# PSU.net
KiCad netlist of a schematic drawn in Altium Designer
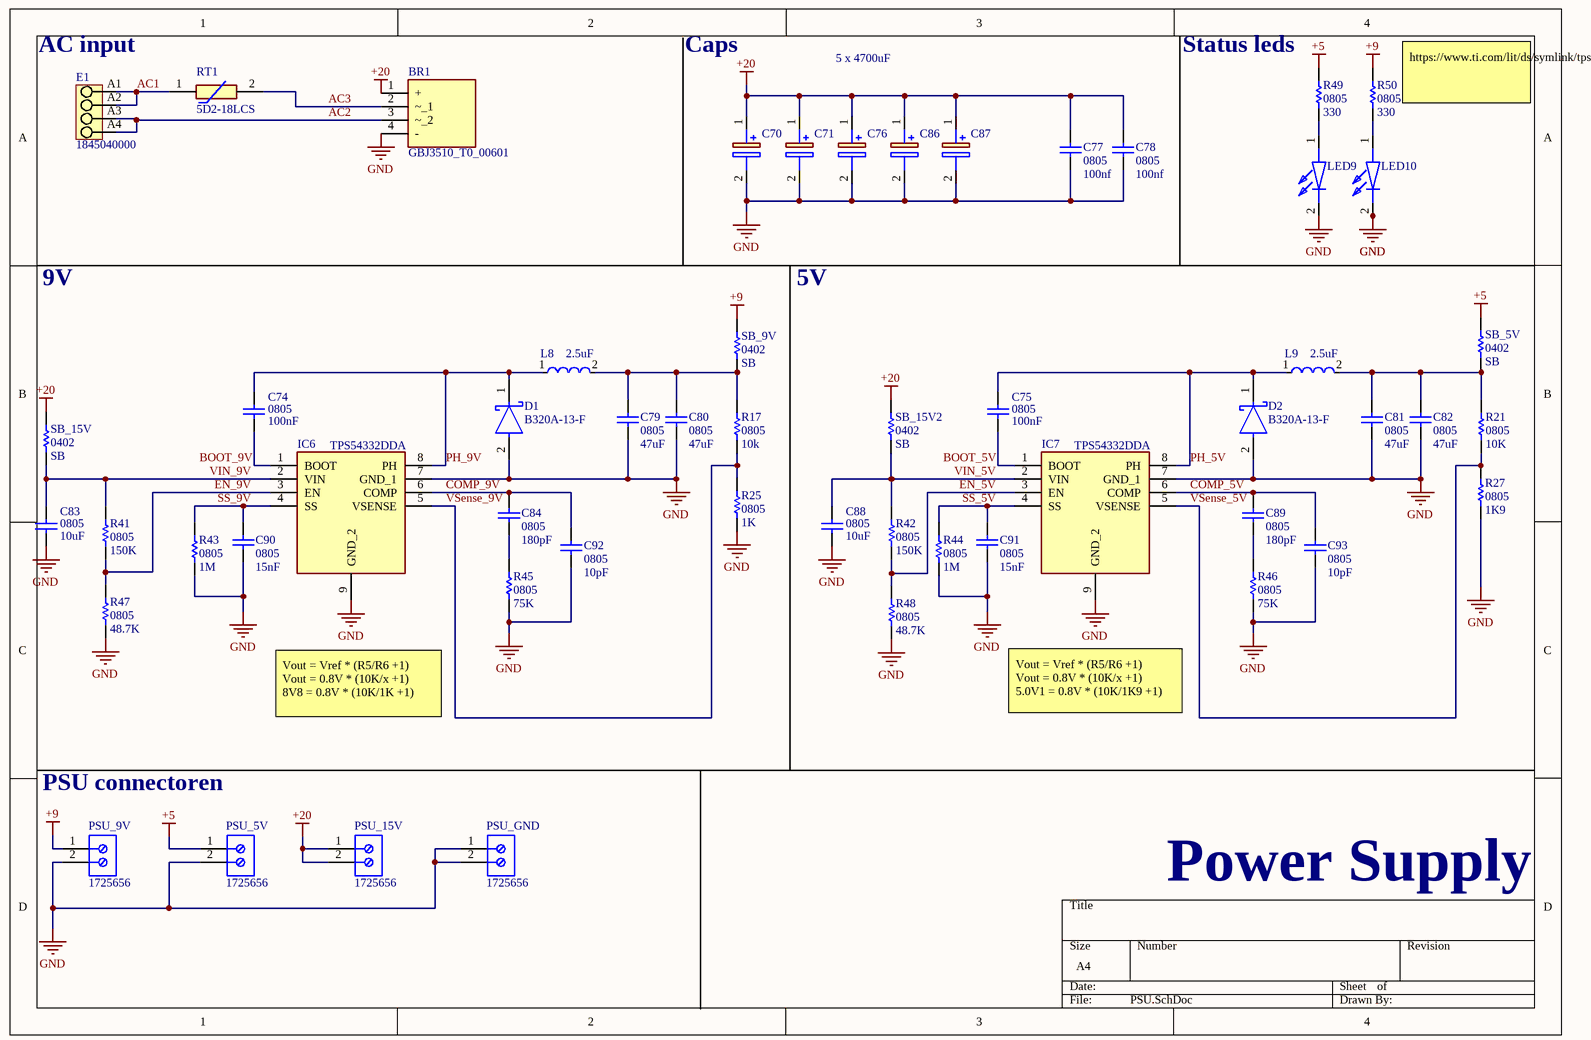
[diagram p0: PSU.SchDoc]

(export (version "E")
  (design (tool "Eeschema 10.0.6"))
  (components
    (comp (ref "BR1")
      (value "GBJ3510_T0_00601")
      (footprint "SamacSys:GBJ3510_T0_00601")
      (description "Bridge Rectifier")
      (fields (field (name "MOUSER PART NUMBER") "241-GBJ3510_T0_00601"))
      (libsource (lib "*") (part "GBJ3510_T0_00601"))
    )
    (comp (ref "C70")
      (value "UFW1V472MHD")
      (footprint "SamacSys:CAPPRD750W80D1825H3750")
      (description "Capacitor Polarised")
      (fields (field (name "MOUSER PART NUMBER") "647-UFW1V472MHD"))
      (libsource (lib "*") (part "UFW1V472MHD"))
    )
    (comp (ref "C71")
      (value "UFW1V472MHD")
      (footprint "SamacSys:CAPPRD750W80D1825H3750")
      (description "Capacitor Polarised")
      (fields (field (name "MOUSER PART NUMBER") "647-UFW1V472MHD"))
      (libsource (lib "*") (part "UFW1V472MHD"))
    )
    (comp (ref "C74")
      (value "0805")
      (footprint "6-0805_N")
      (description "Capacitor")
      (fields (field (name "ALTIUM_VALUE") "100nF") (field (name "PUBLISHER") "Altium Limited"))
      (libsource (lib "Miscellaneous Devices") (part "Cap"))
    )
    (comp (ref "C75")
      (value "0805")
      (footprint "6-0805_N")
      (description "Capacitor")
      (fields (field (name "ALTIUM_VALUE") "100nF") (field (name "PUBLISHER") "Altium Limited"))
      (libsource (lib "Miscellaneous Devices") (part "Cap"))
    )
    (comp (ref "C76")
      (value "UFW1V472MHD")
      (footprint "SamacSys:CAPPRD750W80D1825H3750")
      (description "Capacitor Polarised")
      (fields (field (name "MOUSER PART NUMBER") "647-UFW1V472MHD"))
      (libsource (lib "*") (part "UFW1V472MHD"))
    )
    (comp (ref "C77")
      (value "0805")
      (footprint "6-0805_N")
      (description "Capacitor")
      (fields (field (name "ALTIUM_VALUE") "100nf") (field (name "PUBLISHER") "Altium Limited"))
      (libsource (lib "Miscellaneous Devices") (part "Cap"))
    )
    (comp (ref "C78")
      (value "0805")
      (footprint "6-0805_N")
      (description "Capacitor")
      (fields (field (name "ALTIUM_VALUE") "100nf") (field (name "PUBLISHER") "Altium Limited"))
      (libsource (lib "Miscellaneous Devices") (part "Cap"))
    )
    (comp (ref "C79")
      (value "0805")
      (footprint "6-0805_N")
      (description "Capacitor")
      (fields (field (name "ALTIUM_VALUE") "47uF") (field (name "PUBLISHER") "Altium Limited"))
      (libsource (lib "Miscellaneous Devices") (part "Cap"))
    )
    (comp (ref "C80")
      (value "0805")
      (footprint "6-0805_N")
      (description "Capacitor")
      (fields (field (name "ALTIUM_VALUE") "47uF") (field (name "PUBLISHER") "Altium Limited"))
      (libsource (lib "Miscellaneous Devices") (part "Cap"))
    )
    (comp (ref "C81")
      (value "0805")
      (footprint "6-0805_N")
      (description "Capacitor")
      (fields (field (name "ALTIUM_VALUE") "47uF") (field (name "PUBLISHER") "Altium Limited"))
      (libsource (lib "Miscellaneous Devices") (part "Cap"))
    )
    (comp (ref "C82")
      (value "0805")
      (footprint "6-0805_N")
      (description "Capacitor")
      (fields (field (name "ALTIUM_VALUE") "47uF") (field (name "PUBLISHER") "Altium Limited"))
      (libsource (lib "Miscellaneous Devices") (part "Cap"))
    )
    (comp (ref "C83")
      (value "0805")
      (footprint "6-0805_N")
      (description "Capacitor")
      (fields (field (name "ALTIUM_VALUE") "10uF") (field (name "PUBLISHER") "Altium Limited"))
      (libsource (lib "Miscellaneous Devices") (part "Cap"))
    )
    (comp (ref "C84")
      (value "0805")
      (footprint "6-0805_N")
      (description "Capacitor")
      (fields (field (name "ALTIUM_VALUE") "180pF") (field (name "PUBLISHER") "Altium Limited"))
      (libsource (lib "Miscellaneous Devices") (part "Cap"))
    )
    (comp (ref "C86")
      (value "UFW1V472MHD")
      (footprint "SamacSys:CAPPRD750W80D1825H3750")
      (description "Capacitor Polarised")
      (fields (field (name "MOUSER PART NUMBER") "647-UFW1V472MHD"))
      (libsource (lib "*") (part "UFW1V472MHD"))
    )
    (comp (ref "C87")
      (value "UFW1V472MHD")
      (footprint "SamacSys:CAPPRD750W80D1825H3750")
      (description "Capacitor Polarised")
      (fields (field (name "MOUSER PART NUMBER") "647-UFW1V472MHD"))
      (libsource (lib "*") (part "UFW1V472MHD"))
    )
    (comp (ref "C88")
      (value "0805")
      (footprint "6-0805_N")
      (description "Capacitor")
      (fields (field (name "ALTIUM_VALUE") "10uF") (field (name "PUBLISHER") "Altium Limited"))
      (libsource (lib "Miscellaneous Devices") (part "Cap"))
    )
    (comp (ref "C89")
      (value "0805")
      (footprint "6-0805_N")
      (description "Capacitor")
      (fields (field (name "ALTIUM_VALUE") "180pF") (field (name "PUBLISHER") "Altium Limited"))
      (libsource (lib "Miscellaneous Devices") (part "Cap"))
    )
    (comp (ref "C90")
      (value "0805")
      (footprint "6-0805_N")
      (description "Capacitor")
      (fields (field (name "ALTIUM_VALUE") "15nF") (field (name "PUBLISHER") "Altium Limited"))
      (libsource (lib "Miscellaneous Devices") (part "Cap"))
    )
    (comp (ref "C91")
      (value "0805")
      (footprint "6-0805_N")
      (description "Capacitor")
      (fields (field (name "ALTIUM_VALUE") "15nF") (field (name "PUBLISHER") "Altium Limited"))
      (libsource (lib "Miscellaneous Devices") (part "Cap"))
    )
    (comp (ref "C92")
      (value "0805")
      (footprint "6-0805_N")
      (description "Capacitor")
      (fields (field (name "ALTIUM_VALUE") "10pF") (field (name "PUBLISHER") "Altium Limited"))
      (libsource (lib "Miscellaneous Devices") (part "Cap"))
    )
    (comp (ref "C93")
      (value "0805")
      (footprint "6-0805_N")
      (description "Capacitor")
      (fields (field (name "ALTIUM_VALUE") "10pF") (field (name "PUBLISHER") "Altium Limited"))
      (libsource (lib "Miscellaneous Devices") (part "Cap"))
    )
    (comp (ref "D1")
      (value "B320A-13-F")
      (footprint "FP-SMA-MFG")
      (description "DIODE SCHOTTKY 20V 3A SMA")
      (fields
        (field (name "MANUFACTURER") "Diodes Inc.")
        (field (name "OCTOPART") "https://octopart.com/b320a-13-f-diodes+inc.-325803")
      )
      (libsource (lib "Altium Content Vault") (part "1d6ec82d83fb6aee721767c19dac4b9"))
    )
    (comp (ref "D2")
      (value "B320A-13-F")
      (footprint "FP-SMA-MFG")
      (description "DIODE SCHOTTKY 20V 3A SMA")
      (fields
        (field (name "MANUFACTURER") "Diodes Inc.")
        (field (name "OCTOPART") "https://octopart.com/b320a-13-f-diodes+inc.-325803")
      )
      (libsource (lib "Altium Content Vault") (part "1d6ec82d83fb6aee721767c19dac4b9"))
    )
    (comp (ref "E1")
      (value "1845040000")
      (footprint "LM_3_5_90_04")
      (description "OMNIMATE Signal - series LM")
      (fields (field (name "MANUFACTURER") "Weidmueller"))
      (libsource (lib "Altium Content Vault") (part "Terminal_04_1x04"))
    )
    (comp (ref "IC6")
      (value "TPS54332DDA")
      (footprint "SamacSys:SOIC127P600X170-9N")
      (description "Integrated Circuit")
      (fields (field (name "MOUSER PART NUMBER") "595-TPS54332DDA"))
      (libsource (lib "*") (part "TPS54332DDA"))
    )
    (comp (ref "IC7")
      (value "TPS54332DDA")
      (footprint "SamacSys:SOIC127P600X170-9N")
      (description "Integrated Circuit")
      (fields (field (name "MOUSER PART NUMBER") "595-TPS54332DDA"))
      (libsource (lib "*") (part "TPS54332DDA"))
    )
    (comp (ref "L8")
      (value "2.5uF")
      (footprint "710-74437346025")
      (description "SMD")
      (libsource (lib "AMP") (part "710-74437346025"))
    )
    (comp (ref "L9")
      (value "2.5uF")
      (footprint "710-74437346025")
      (description "SMD")
      (libsource (lib "AMP") (part "710-74437346025"))
    )
    (comp (ref "LED9")
      (value "ELM70303GD")
      (footprint "SamacSys:ELM70303GD")
      (description "LED")
      (fields (field (name "MOUSER PART NUMBER") "749-ELM70303GD"))
      (libsource (lib "SamacSys") (part "ELM70303GD"))
    )
    (comp (ref "LED10")
      (value "ELM70303GD")
      (footprint "SamacSys:ELM70303GD")
      (description "LED")
      (fields (field (name "MOUSER PART NUMBER") "749-ELM70303GD"))
      (libsource (lib "SamacSys") (part "ELM70303GD"))
    )
    (comp (ref "PSU_5V")
      (value "1725656")
      (footprint "PHOE-1725656-2")
      (description "Male Header, Pitch 2.54 mm, 1 x 2 Position, Height 9 mm, Tail Length 3.5 mm")
      (fields (field (name "MANUFACTURER") "Phoenix Contact"))
      (libsource (lib "Altium Content Vault") (part "CN-1P-F-TB2"))
    )
    (comp (ref "PSU_9V")
      (value "1725656")
      (footprint "PHOE-1725656-2")
      (description "Male Header, Pitch 2.54 mm, 1 x 2 Position, Height 9 mm, Tail Length 3.5 mm")
      (fields (field (name "MANUFACTURER") "Phoenix Contact"))
      (libsource (lib "Altium Content Vault") (part "CN-1P-F-TB2"))
    )
    (comp (ref "PSU_15V")
      (value "1725656")
      (footprint "PHOE-1725656-2")
      (description "Male Header, Pitch 2.54 mm, 1 x 2 Position, Height 9 mm, Tail Length 3.5 mm")
      (fields (field (name "MANUFACTURER") "Phoenix Contact"))
      (libsource (lib "Altium Content Vault") (part "CN-1P-F-TB2"))
    )
    (comp (ref "PSU_GND")
      (value "1725656")
      (footprint "PHOE-1725656-2")
      (description "Male Header, Pitch 2.54 mm, 1 x 2 Position, Height 9 mm, Tail Length 3.5 mm")
      (fields (field (name "MANUFACTURER") "Phoenix Contact"))
      (libsource (lib "Altium Content Vault") (part "CN-1P-F-TB2"))
    )
    (comp (ref "R17")
      (value "0805")
      (footprint "6-0805_N")
      (description "Resistor")
      (fields (field (name "ALTIUM_VALUE") "10k") (field (name "PUBLISHER") "Altium Limited"))
      (libsource (lib "Miscellaneous Devices") (part "Res1"))
    )
    (comp (ref "R21")
      (value "0805")
      (footprint "6-0805_N")
      (description "Resistor")
      (fields (field (name "ALTIUM_VALUE") "10K") (field (name "PUBLISHER") "Altium Limited"))
      (libsource (lib "Miscellaneous Devices") (part "Res1"))
    )
    (comp (ref "R25")
      (value "0805")
      (footprint "6-0805_N")
      (description "Resistor")
      (fields (field (name "ALTIUM_VALUE") "1K") (field (name "PUBLISHER") "Altium Limited"))
      (libsource (lib "Miscellaneous Devices") (part "Res1"))
    )
    (comp (ref "R27")
      (value "0805")
      (footprint "6-0805_N")
      (description "Resistor")
      (fields (field (name "ALTIUM_VALUE") "1K9") (field (name "PUBLISHER") "Altium Limited"))
      (libsource (lib "Miscellaneous Devices") (part "Res1"))
    )
    (comp (ref "R41")
      (value "0805")
      (footprint "6-0805_N")
      (description "Resistor")
      (fields (field (name "ALTIUM_VALUE") "150K") (field (name "PUBLISHER") "Altium Limited"))
      (libsource (lib "Miscellaneous Devices") (part "Res1"))
    )
    (comp (ref "R42")
      (value "0805")
      (footprint "6-0805_N")
      (description "Resistor")
      (fields (field (name "ALTIUM_VALUE") "150K") (field (name "PUBLISHER") "Altium Limited"))
      (libsource (lib "Miscellaneous Devices") (part "Res1"))
    )
    (comp (ref "R43")
      (value "0805")
      (footprint "6-0805_N")
      (description "Resistor")
      (fields (field (name "ALTIUM_VALUE") "1M") (field (name "PUBLISHER") "Altium Limited"))
      (libsource (lib "Miscellaneous Devices") (part "Res1"))
    )
    (comp (ref "R44")
      (value "0805")
      (footprint "6-0805_N")
      (description "Resistor")
      (fields (field (name "ALTIUM_VALUE") "1M") (field (name "PUBLISHER") "Altium Limited"))
      (libsource (lib "Miscellaneous Devices") (part "Res1"))
    )
    (comp (ref "R45")
      (value "0805")
      (footprint "6-0805_N")
      (description "Resistor")
      (fields (field (name "ALTIUM_VALUE") "75K") (field (name "PUBLISHER") "Altium Limited"))
      (libsource (lib "Miscellaneous Devices") (part "Res1"))
    )
    (comp (ref "R46")
      (value "0805")
      (footprint "6-0805_N")
      (description "Resistor")
      (fields (field (name "ALTIUM_VALUE") "75K") (field (name "PUBLISHER") "Altium Limited"))
      (libsource (lib "Miscellaneous Devices") (part "Res1"))
    )
    (comp (ref "R47")
      (value "0805")
      (footprint "6-0805_N")
      (description "Resistor")
      (fields (field (name "ALTIUM_VALUE") "48.7K") (field (name "PUBLISHER") "Altium Limited"))
      (libsource (lib "Miscellaneous Devices") (part "Res1"))
    )
    (comp (ref "R48")
      (value "0805")
      (footprint "6-0805_N")
      (description "Resistor")
      (fields (field (name "ALTIUM_VALUE") "48.7K") (field (name "PUBLISHER") "Altium Limited"))
      (libsource (lib "Miscellaneous Devices") (part "Res1"))
    )
    (comp (ref "R49")
      (value "0805")
      (footprint "6-0805_N")
      (description "Resistor")
      (fields (field (name "ALTIUM_VALUE") "330") (field (name "PUBLISHER") "Altium Limited"))
      (libsource (lib "Miscellaneous Devices") (part "Res1"))
    )
    (comp (ref "R50")
      (value "0805")
      (footprint "6-0805_N")
      (description "Resistor")
      (fields (field (name "ALTIUM_VALUE") "330") (field (name "PUBLISHER") "Altium Limited"))
      (libsource (lib "Miscellaneous Devices") (part "Res1"))
    )
    (comp (ref "RT1")
      (value "5D2-18LCS")
      (footprint "SamacSys:5D218LCS")
      (description "Thermistor")
      (fields (field (name "MOUSER PART NUMBER") "954-5D2-18LCS"))
      (libsource (lib "*") (part "5D2-18LCS"))
    )
    (comp (ref "SB_5V")
      (value "0402")
      (footprint "0402")
      (description "Resistor")
      (fields (field (name "ALTIUM_VALUE") "SB") (field (name "PUBLISHER") "Altium Limited"))
      (libsource (lib "Miscellaneous Devices") (part "Res1"))
    )
    (comp (ref "SB_9V")
      (value "0402")
      (footprint "0402")
      (description "Resistor")
      (fields (field (name "ALTIUM_VALUE") "SB") (field (name "PUBLISHER") "Altium Limited"))
      (libsource (lib "Miscellaneous Devices") (part "Res1"))
    )
    (comp (ref "SB_15V")
      (value "0402")
      (footprint "0402")
      (description "Resistor")
      (fields (field (name "ALTIUM_VALUE") "SB") (field (name "PUBLISHER") "Altium Limited"))
      (libsource (lib "Miscellaneous Devices") (part "Res1"))
    )
    (comp (ref "SB_15V2")
      (value "0402")
      (footprint "0402")
      (description "Resistor")
      (fields (field (name "ALTIUM_VALUE") "SB") (field (name "PUBLISHER") "Altium Limited"))
      (libsource (lib "Miscellaneous Devices") (part "Res1"))
    )
  )
  (nets
    (net (code "1") (name "+5") (class "Default")
      (node (ref "PSU_5V") (pin "1") (pinfunction "1_1") (pintype "passive"))
      (node (ref "R49") (pin "1") (pinfunction "1_1") (pintype "passive"))
      (node (ref "SB_5V") (pin "1") (pinfunction "1_1") (pintype "passive"))
    )
    (net (code "2") (name "+9") (class "Default")
      (node (ref "PSU_9V") (pin "1") (pinfunction "1_1") (pintype "passive"))
      (node (ref "R50") (pin "1") (pinfunction "1_1") (pintype "passive"))
      (node (ref "SB_9V") (pin "2") (pinfunction "2_2") (pintype "passive"))
    )
    (net (code "3") (name "+20") (class "Default")
      (node (ref "BR1") (pin "1") (pinfunction "+_1") (pintype "passive"))
      (node (ref "C70") (pin "1") (pinfunction "+_1") (pintype "passive"))
      (node (ref "C71") (pin "1") (pinfunction "+_1") (pintype "passive"))
      (node (ref "C76") (pin "1") (pinfunction "+_1") (pintype "passive"))
      (node (ref "C77") (pin "1") (pinfunction "1_1") (pintype "passive"))
      (node (ref "C78") (pin "1") (pinfunction "1_1") (pintype "passive"))
      (node (ref "C86") (pin "1") (pinfunction "+_1") (pintype "passive"))
      (node (ref "C87") (pin "1") (pinfunction "+_1") (pintype "passive"))
      (node (ref "PSU_15V") (pin "1") (pinfunction "1_1") (pintype "passive"))
      (node (ref "PSU_15V") (pin "2") (pinfunction "2_2") (pintype "passive"))
      (node (ref "SB_15V") (pin "1") (pinfunction "1_1") (pintype "passive"))
      (node (ref "SB_15V2") (pin "2") (pinfunction "2_2") (pintype "passive"))
    )
    (net (code "4") (name "/AC1") (class "Default")
      (node (ref "E1") (pin "A1") (pinfunction "A1_A1") (pintype "passive"))
      (node (ref "E1") (pin "A2") (pinfunction "A2_A2") (pintype "passive"))
      (node (ref "RT1") (pin "1") (pinfunction "1_1") (pintype "passive"))
    )
    (net (code "5") (name "/AC2") (class "Default")
      (node (ref "BR1") (pin "3") (pinfunction "~_2_3") (pintype "passive"))
      (node (ref "E1") (pin "A3") (pinfunction "A3_A3") (pintype "passive"))
      (node (ref "E1") (pin "A4") (pinfunction "A4_A4") (pintype "passive"))
    )
    (net (code "6") (name "/AC3") (class "Default")
      (node (ref "BR1") (pin "2") (pinfunction "~_1_2") (pintype "passive"))
      (node (ref "RT1") (pin "2") (pinfunction "2_2") (pintype "passive"))
    )
    (net (code "7") (name "/BOOT_5V") (class "Default")
      (node (ref "C75") (pin "1") (pinfunction "1_1") (pintype "passive"))
      (node (ref "IC7") (pin "1") (pinfunction "BOOT_1") (pintype "passive"))
    )
    (net (code "8") (name "/BOOT_9V") (class "Default")
      (node (ref "C74") (pin "1") (pinfunction "1_1") (pintype "passive"))
      (node (ref "IC6") (pin "1") (pinfunction "BOOT_1") (pintype "passive"))
    )
    (net (code "9") (name "/COMP_5V") (class "Default")
      (node (ref "C89") (pin "2") (pinfunction "2_2") (pintype "passive"))
      (node (ref "C93") (pin "2") (pinfunction "2_2") (pintype "passive"))
      (node (ref "IC7") (pin "6") (pinfunction "COMP_6") (pintype "passive"))
    )
    (net (code "10") (name "/COMP_9V") (class "Default")
      (node (ref "C84") (pin "2") (pinfunction "2_2") (pintype "passive"))
      (node (ref "C92") (pin "2") (pinfunction "2_2") (pintype "passive"))
      (node (ref "IC6") (pin "6") (pinfunction "COMP_6") (pintype "passive"))
    )
    (net (code "11") (name "/EN_5V") (class "Default")
      (node (ref "IC7") (pin "3") (pinfunction "EN_3") (pintype "passive"))
      (node (ref "R42") (pin "2") (pinfunction "2_2") (pintype "passive"))
      (node (ref "R48") (pin "1") (pinfunction "1_1") (pintype "passive"))
    )
    (net (code "12") (name "/EN_9V") (class "Default")
      (node (ref "IC6") (pin "3") (pinfunction "EN_3") (pintype "passive"))
      (node (ref "R41") (pin "2") (pinfunction "2_2") (pintype "passive"))
      (node (ref "R47") (pin "1") (pinfunction "1_1") (pintype "passive"))
    )
    (net (code "13") (name "/PH_5V") (class "Default")
      (node (ref "C75") (pin "2") (pinfunction "2_2") (pintype "passive"))
      (node (ref "D2") (pin "1") (pinfunction "C_1") (pintype "passive"))
      (node (ref "IC7") (pin "8") (pinfunction "PH_8") (pintype "passive"))
      (node (ref "L9") (pin "1") (pintype "passive"))
    )
    (net (code "14") (name "/PH_9V") (class "Default")
      (node (ref "C74") (pin "2") (pinfunction "2_2") (pintype "passive"))
      (node (ref "D1") (pin "1") (pinfunction "C_1") (pintype "passive"))
      (node (ref "IC6") (pin "8") (pinfunction "PH_8") (pintype "passive"))
      (node (ref "L8") (pin "1") (pintype "passive"))
    )
    (net (code "15") (name "/SS_5V") (class "Default")
      (node (ref "C91") (pin "2") (pinfunction "2_2") (pintype "passive"))
      (node (ref "IC7") (pin "4") (pinfunction "SS_4") (pintype "passive"))
      (node (ref "R44") (pin "1") (pinfunction "1_1") (pintype "passive"))
    )
    (net (code "16") (name "/SS_9V") (class "Default")
      (node (ref "C90") (pin "2") (pinfunction "2_2") (pintype "passive"))
      (node (ref "IC6") (pin "4") (pinfunction "SS_4") (pintype "passive"))
      (node (ref "R43") (pin "1") (pinfunction "1_1") (pintype "passive"))
    )
    (net (code "17") (name "/VIN_5V") (class "Default")
      (node (ref "C88") (pin "2") (pinfunction "2_2") (pintype "passive"))
      (node (ref "IC7") (pin "2") (pinfunction "VIN_2") (pintype "passive"))
      (node (ref "R42") (pin "1") (pinfunction "1_1") (pintype "passive"))
      (node (ref "SB_15V2") (pin "1") (pinfunction "1_1") (pintype "passive"))
    )
    (net (code "18") (name "/VIN_9V") (class "Default")
      (node (ref "C83") (pin "2") (pinfunction "2_2") (pintype "passive"))
      (node (ref "IC6") (pin "2") (pinfunction "VIN_2") (pintype "passive"))
      (node (ref "R41") (pin "1") (pinfunction "1_1") (pintype "passive"))
      (node (ref "SB_15V") (pin "2") (pinfunction "2_2") (pintype "passive"))
    )
    (net (code "19") (name "/VSense_5V") (class "Default")
      (node (ref "IC7") (pin "5") (pinfunction "VSENSE_5") (pintype "passive"))
      (node (ref "R21") (pin "2") (pinfunction "2_2") (pintype "passive"))
      (node (ref "R27") (pin "1") (pinfunction "1_1") (pintype "passive"))
    )
    (net (code "20") (name "/VSense_9V") (class "Default")
      (node (ref "IC6") (pin "5") (pinfunction "VSENSE_5") (pintype "passive"))
      (node (ref "R17") (pin "2") (pinfunction "2_2") (pintype "passive"))
      (node (ref "R25") (pin "1") (pinfunction "1_1") (pintype "passive"))
    )
    (net (code "21") (name "GND") (class "Default")
      (node (ref "BR1") (pin "4") (pinfunction "-_4") (pintype "passive"))
      (node (ref "C70") (pin "2") (pinfunction "-_2") (pintype "passive"))
      (node (ref "C71") (pin "2") (pinfunction "-_2") (pintype "passive"))
      (node (ref "C76") (pin "2") (pinfunction "-_2") (pintype "passive"))
      (node (ref "C77") (pin "2") (pinfunction "2_2") (pintype "passive"))
      (node (ref "C78") (pin "2") (pinfunction "2_2") (pintype "passive"))
      (node (ref "C79") (pin "1") (pinfunction "1_1") (pintype "passive"))
      (node (ref "C80") (pin "1") (pinfunction "1_1") (pintype "passive"))
      (node (ref "C81") (pin "1") (pinfunction "1_1") (pintype "passive"))
      (node (ref "C82") (pin "1") (pinfunction "1_1") (pintype "passive"))
      (node (ref "C83") (pin "1") (pinfunction "1_1") (pintype "passive"))
      (node (ref "C86") (pin "2") (pinfunction "-_2") (pintype "passive"))
      (node (ref "C87") (pin "2") (pinfunction "-_2") (pintype "passive"))
      (node (ref "C88") (pin "1") (pinfunction "1_1") (pintype "passive"))
      (node (ref "C90") (pin "1") (pinfunction "1_1") (pintype "passive"))
      (node (ref "C91") (pin "1") (pinfunction "1_1") (pintype "passive"))
      (node (ref "C92") (pin "1") (pinfunction "1_1") (pintype "passive"))
      (node (ref "C93") (pin "1") (pinfunction "1_1") (pintype "passive"))
      (node (ref "D1") (pin "2") (pinfunction "A_2") (pintype "passive"))
      (node (ref "D2") (pin "2") (pinfunction "A_2") (pintype "passive"))
      (node (ref "IC6") (pin "7") (pinfunction "GND_1_7") (pintype "passive"))
      (node (ref "IC6") (pin "9") (pinfunction "GND_2_9") (pintype "passive"))
      (node (ref "IC7") (pin "7") (pinfunction "GND_1_7") (pintype "passive"))
      (node (ref "IC7") (pin "9") (pinfunction "GND_2_9") (pintype "passive"))
      (node (ref "LED10") (pin "2") (pinfunction "K_2") (pintype "passive"))
      (node (ref "LED9") (pin "2") (pinfunction "K_2") (pintype "passive"))
      (node (ref "PSU_5V") (pin "2") (pinfunction "2_2") (pintype "passive"))
      (node (ref "PSU_9V") (pin "2") (pinfunction "2_2") (pintype "passive"))
      (node (ref "PSU_GND") (pin "1") (pinfunction "1_1") (pintype "passive"))
      (node (ref "PSU_GND") (pin "2") (pinfunction "2_2") (pintype "passive"))
      (node (ref "R25") (pin "2") (pinfunction "2_2") (pintype "passive"))
      (node (ref "R27") (pin "2") (pinfunction "2_2") (pintype "passive"))
      (node (ref "R43") (pin "2") (pinfunction "2_2") (pintype "passive"))
      (node (ref "R44") (pin "2") (pinfunction "2_2") (pintype "passive"))
      (node (ref "R45") (pin "2") (pinfunction "2_2") (pintype "passive"))
      (node (ref "R46") (pin "2") (pinfunction "2_2") (pintype "passive"))
      (node (ref "R47") (pin "2") (pinfunction "2_2") (pintype "passive"))
      (node (ref "R48") (pin "2") (pinfunction "2_2") (pintype "passive"))
    )
    (net (code "22") (name "Net-(C79-Pad2)") (class "Default")
      (node (ref "C79") (pin "2") (pinfunction "2_2") (pintype "passive"))
      (node (ref "C80") (pin "2") (pinfunction "2_2") (pintype "passive"))
      (node (ref "L8") (pin "2") (pintype "passive"))
      (node (ref "R17") (pin "1") (pinfunction "1_1") (pintype "passive"))
      (node (ref "SB_9V") (pin "1") (pinfunction "1_1") (pintype "passive"))
    )
    (net (code "23") (name "Net-(C81-Pad2)") (class "Default")
      (node (ref "C81") (pin "2") (pinfunction "2_2") (pintype "passive"))
      (node (ref "C82") (pin "2") (pinfunction "2_2") (pintype "passive"))
      (node (ref "L9") (pin "2") (pintype "passive"))
      (node (ref "R21") (pin "1") (pinfunction "1_1") (pintype "passive"))
      (node (ref "SB_5V") (pin "2") (pinfunction "2_2") (pintype "passive"))
    )
    (net (code "24") (name "Net-(C84-Pad1)") (class "Default")
      (node (ref "C84") (pin "1") (pinfunction "1_1") (pintype "passive"))
      (node (ref "R45") (pin "1") (pinfunction "1_1") (pintype "passive"))
    )
    (net (code "25") (name "Net-(C89-Pad1)") (class "Default")
      (node (ref "C89") (pin "1") (pinfunction "1_1") (pintype "passive"))
      (node (ref "R46") (pin "1") (pinfunction "1_1") (pintype "passive"))
    )
    (net (code "26") (name "Net-(LED9-A)") (class "Default")
      (node (ref "LED9") (pin "1") (pinfunction "A_1") (pintype "passive"))
      (node (ref "R49") (pin "2") (pinfunction "2_2") (pintype "passive"))
    )
    (net (code "27") (name "Net-(LED10-A)") (class "Default")
      (node (ref "LED10") (pin "1") (pinfunction "A_1") (pintype "passive"))
      (node (ref "R50") (pin "2") (pinfunction "2_2") (pintype "passive"))
    )
  )
)
